# Microcontrolador.net
KiCad netlist of a schematic drawn in Altium Designer
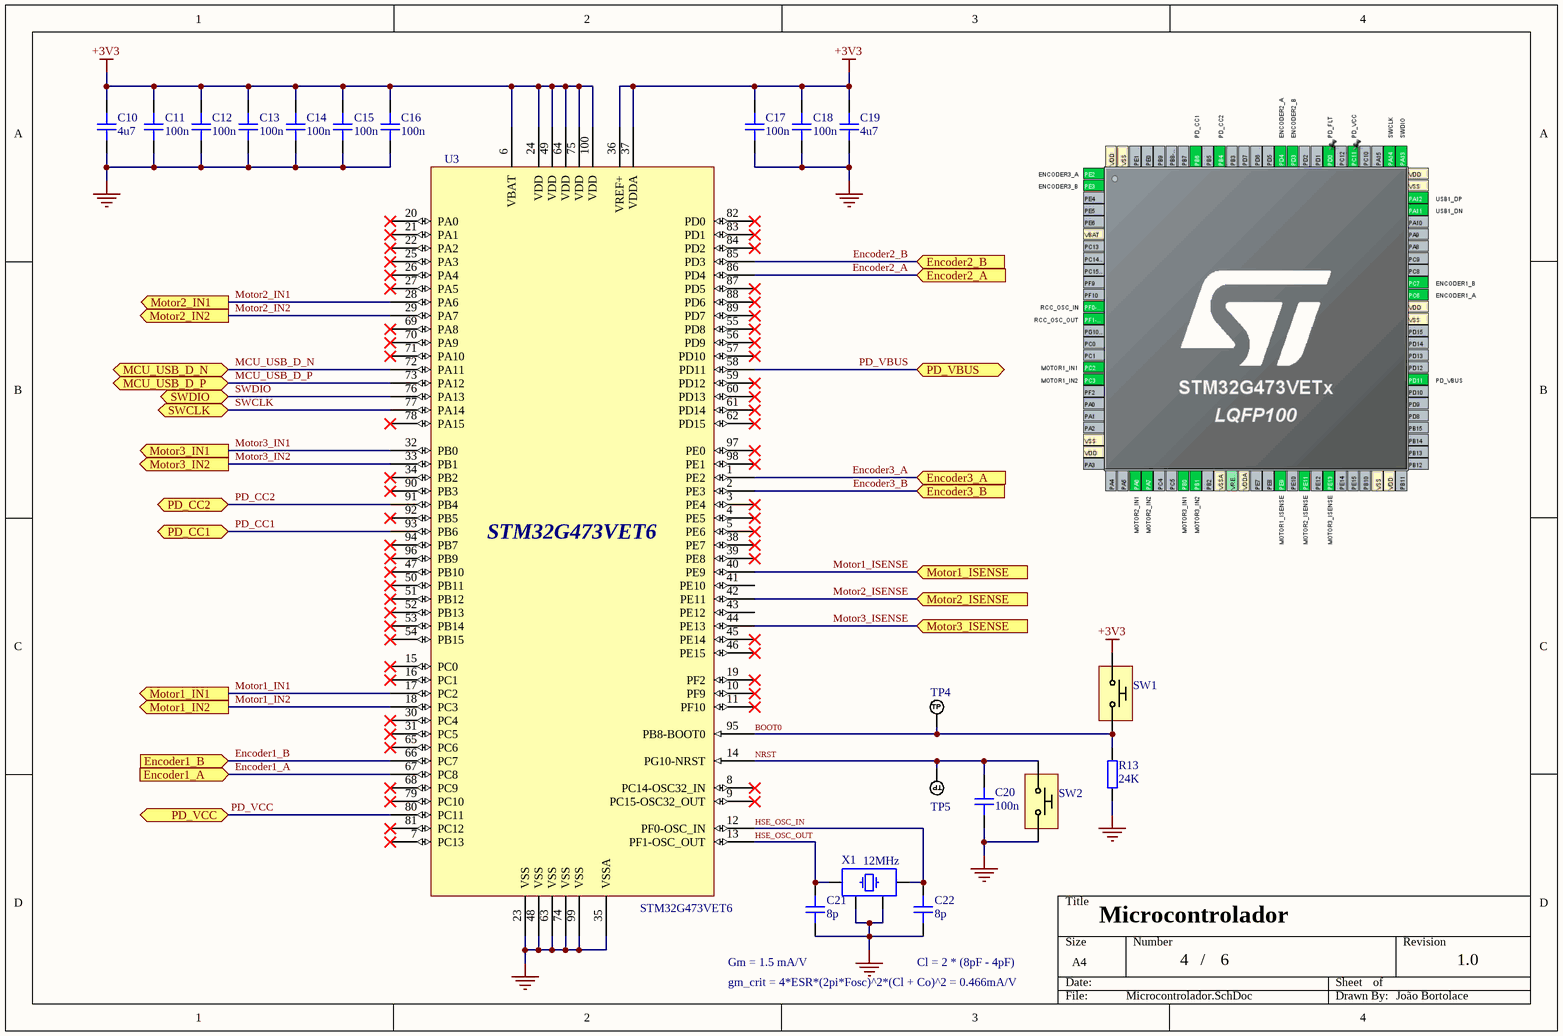
[diagram p0: Microcontrolador.SchDoc]

(export (version "E")
  (design (tool "Eeschema 10.0.6"))
  (components
    (comp (ref "C10")
      (value "4u7")
      (footprint "CAP_0805")
      (description "4.7uF ±10% 50V Ceramic Capacitor X5R 0805")
      (fields
        (field (name "MANUFACTURER") "Samsung Electro-Mechanics")
        (field (name "MANUFACTURER PART NUMBER") "CL21A475KBQNNNE")
      )
      (libsource (lib "Schematic-Lib-PhilsLab") (part "CAP_0805"))
    )
    (comp (ref "C11")
      (value "100n")
      (footprint "CAP_0402")
      (description "100nF ±10% 50V Ceramic Capacitor X7R 0402D 0402")
      (fields
        (field (name "MANUFACTURER") "muRata")
        (field (name "MANUFACTURER PART NUMBER") "GRM155R71H104KE14D")
      )
      (libsource (lib "Schematic-Lib-PhilsLab") (part "CAP_0402"))
    )
    (comp (ref "C12")
      (value "100n")
      (footprint "CAP_0402")
      (description "100nF ±10% 50V Ceramic Capacitor X7R 0402D 0402")
      (fields
        (field (name "MANUFACTURER") "muRata")
        (field (name "MANUFACTURER PART NUMBER") "GRM155R71H104KE14D")
      )
      (libsource (lib "Schematic-Lib-PhilsLab") (part "CAP_0402"))
    )
    (comp (ref "C13")
      (value "100n")
      (footprint "CAP_0402")
      (description "100nF ±10% 50V Ceramic Capacitor X7R 0402D 0402")
      (fields
        (field (name "MANUFACTURER") "muRata")
        (field (name "MANUFACTURER PART NUMBER") "GRM155R71H104KE14D")
      )
      (libsource (lib "Schematic-Lib-PhilsLab") (part "CAP_0402"))
    )
    (comp (ref "C14")
      (value "100n")
      (footprint "CAP_0402")
      (description "100nF ±10% 50V Ceramic Capacitor X7R 0402D 0402")
      (fields
        (field (name "MANUFACTURER") "muRata")
        (field (name "MANUFACTURER PART NUMBER") "GRM155R71H104KE14D")
      )
      (libsource (lib "Schematic-Lib-PhilsLab") (part "CAP_0402"))
    )
    (comp (ref "C15")
      (value "100n")
      (footprint "CAP_0402")
      (description "100nF ±10% 50V Ceramic Capacitor X7R 0402D 0402")
      (fields
        (field (name "MANUFACTURER") "muRata")
        (field (name "MANUFACTURER PART NUMBER") "GRM155R71H104KE14D")
      )
      (libsource (lib "Schematic-Lib-PhilsLab") (part "CAP_0402"))
    )
    (comp (ref "C16")
      (value "100n")
      (footprint "CAP_0402")
      (description "100nF ±10% 50V Ceramic Capacitor X7R 0402D 0402")
      (fields
        (field (name "MANUFACTURER") "muRata")
        (field (name "MANUFACTURER PART NUMBER") "GRM155R71H104KE14D")
      )
      (libsource (lib "Schematic-Lib-PhilsLab") (part "CAP_0402"))
    )
    (comp (ref "C17")
      (value "100n")
      (footprint "CAP_0402")
      (description "100nF ±10% 50V Ceramic Capacitor X7R 0402D 0402")
      (fields
        (field (name "MANUFACTURER") "muRata")
        (field (name "MANUFACTURER PART NUMBER") "GRM155R71H104KE14D")
      )
      (libsource (lib "Schematic-Lib-PhilsLab") (part "CAP_0402"))
    )
    (comp (ref "C18")
      (value "100n")
      (footprint "CAP_0402")
      (description "100nF ±10% 50V Ceramic Capacitor X7R 0402D 0402")
      (fields
        (field (name "MANUFACTURER") "muRata")
        (field (name "MANUFACTURER PART NUMBER") "GRM155R71H104KE14D")
      )
      (libsource (lib "Schematic-Lib-PhilsLab") (part "CAP_0402"))
    )
    (comp (ref "C19")
      (value "4u7")
      (footprint "CAP_0805")
      (description "4.7uF ±10% 50V Ceramic Capacitor X5R 0805")
      (fields
        (field (name "MANUFACTURER") "Samsung Electro-Mechanics")
        (field (name "MANUFACTURER PART NUMBER") "CL21A475KBQNNNE")
      )
      (libsource (lib "Schematic-Lib-PhilsLab") (part "CAP_0805"))
    )
    (comp (ref "C20")
      (value "100n")
      (footprint "CAP_0402")
      (description "100nF ±10% 50V Ceramic Capacitor X7R 0402D 0402")
      (fields
        (field (name "MANUFACTURER") "muRata")
        (field (name "MANUFACTURER PART NUMBER") "GRM155R71H104KE14D")
      )
      (libsource (lib "Schematic-Lib-PhilsLab") (part "CAP_0402"))
    )
    (comp (ref "C21")
      (value "8p")
      (footprint "CAP_0402")
      (description "8pF ±1% 50V Ceramic Capacitor C0G 0402")
      (fields
        (field (name "MANUFACTURER") "muRata")
        (field (name "MANUFACTURER PART NUMBER") "GCM1555C1H8R0FA16D")
      )
      (libsource (lib "Schematic-Lib-PhilsLab") (part "CAP_0402"))
    )
    (comp (ref "C22")
      (value "8p")
      (footprint "CAP_0402")
      (description "8pF ±1% 50V Ceramic Capacitor C0G 0402")
      (fields
        (field (name "MANUFACTURER") "muRata")
        (field (name "MANUFACTURER PART NUMBER") "GCM1555C1H8R0FA16D")
      )
      (libsource (lib "Schematic-Lib-PhilsLab") (part "CAP_0402"))
    )
    (comp (ref "R13")
      (value "24K")
      (footprint "RES_0402")
      (description "Resistor SMD 0402")
      (libsource (lib "Schematic-Lib-PhilsLab") (part "RES_0402"))
    )
    (comp (ref "SW1")
      (value "BOOT")
      (footprint "PTS815")
      (description "Tactile Switch SPST 400gf 2.5mm 4.2mm x 3.2mm Surface Mount")
      (fields
        (field (name "MANUFACTURER") "G-Switch")
        (field (name "MANUFACTURER PART NUMBER") "GT-TC048D-H025-L1")
      )
      (libsource (lib "Schematic-Lib-PhilsLab") (part "PTS815-SJM-250-SMTR-LFS"))
    )
    (comp (ref "SW2")
      (value "RST")
      (footprint "PTS815")
      (description "Tactile Switch SPST 400gf 2.5mm 4.2mm x 3.2mm Surface Mount")
      (fields
        (field (name "MANUFACTURER") "G-Switch")
        (field (name "MANUFACTURER PART NUMBER") "GT-TC048D-H025-L1")
      )
      (libsource (lib "Schematic-Lib-PhilsLab") (part "PTS815-SJM-250-SMTR-LFS"))
    )
    (comp (ref "TP4")
      (value "TP_NOBOM")
      (footprint "PAD_RND_1MM")
      (description "Test Point Round 1mm (NO BOM)")
      (libsource (lib "Schematic-Lib-PhilsLab") (part "TEST_POINT_RND_1MM"))
    )
    (comp (ref "TP5")
      (value "TP_NOBOM")
      (footprint "PAD_RND_1MM")
      (description "Test Point Round 1mm (NO BOM)")
      (libsource (lib "Schematic-Lib-PhilsLab") (part "TEST_POINT_RND_1MM"))
    )
    (comp (ref "U3")
      (value "STM32G473VET6")
      (footprint "LQFP100")
      (fields (field (name "MANUFACTURER") "STMicroelectronics"))
      (libsource (lib "Schematic-Lib-PhilsLab") (part "STM32G473VET6"))
    )
    (comp (ref "X1")
      (value "12MHz")
      (footprint "XTAL_3225")
      (description "Crystal 12MHz ±15ppm 8pF 120Ω SMD3225-4P")
      (fields (field (name "MANUFACTURER") "DIODES") (field (name "MANUFACTURER PART NUMBER") "FL1200138"))
      (libsource (lib "Schematic-Lib-PhilsLab") (part "TSX-3225_24.0000MF15X-AC"))
    )
  )
  (nets
    (net (code "1") (name "+3V3") (class "Default")
      (node (ref "C10") (pin "2") (pinfunction "2_2") (pintype "passive"))
      (node (ref "C11") (pin "2") (pinfunction "2_2") (pintype "passive"))
      (node (ref "C12") (pin "2") (pinfunction "2_2") (pintype "passive"))
      (node (ref "C13") (pin "2") (pinfunction "2_2") (pintype "passive"))
      (node (ref "C14") (pin "2") (pinfunction "2_2") (pintype "passive"))
      (node (ref "C15") (pin "2") (pinfunction "2_2") (pintype "passive"))
      (node (ref "C16") (pin "2") (pinfunction "2_2") (pintype "passive"))
      (node (ref "C17") (pin "2") (pinfunction "2_2") (pintype "passive"))
      (node (ref "C18") (pin "2") (pinfunction "2_2") (pintype "passive"))
      (node (ref "C19") (pin "2") (pinfunction "2_2") (pintype "passive"))
      (node (ref "SW1") (pin "1") (pinfunction "1_1") (pintype "passive"))
      (node (ref "U3") (pin "100") (pinfunction "VDD_100") (pintype "power_in"))
      (node (ref "U3") (pin "24") (pinfunction "VDD_24") (pintype "power_in"))
      (node (ref "U3") (pin "36") (pinfunction "VREF+_36") (pintype "power_in"))
      (node (ref "U3") (pin "37") (pinfunction "VDDA_37") (pintype "power_in"))
      (node (ref "U3") (pin "49") (pinfunction "VDD_49") (pintype "power_in"))
      (node (ref "U3") (pin "6") (pinfunction "VBAT_6") (pintype "power_in"))
      (node (ref "U3") (pin "64") (pinfunction "VDD_64") (pintype "power_in"))
      (node (ref "U3") (pin "75") (pinfunction "VDD_75") (pintype "power_in"))
    )
    (net (code "2") (name "/BOOT0") (class "Default")
      (node (ref "R13") (pin "2") (pinfunction "2_2") (pintype "passive"))
      (node (ref "SW1") (pin "2") (pinfunction "2_2") (pintype "passive"))
      (node (ref "TP4") (pin "1") (pinfunction "TP_1") (pintype "passive"))
      (node (ref "U3") (pin "95") (pinfunction "PB8-BOOT0_95") (pintype "input"))
    )
    (net (code "3") (name "/Encoder1_A") (class "Default")
      (node (ref "U3") (pin "67") (pinfunction "PC8_67") (pintype "bidirectional"))
    )
    (net (code "4") (name "/Encoder1_B") (class "Default")
      (node (ref "U3") (pin "66") (pinfunction "PC7_66") (pintype "bidirectional"))
    )
    (net (code "5") (name "/Encoder2_A") (class "Default")
      (node (ref "U3") (pin "86") (pinfunction "PD4_86") (pintype "bidirectional"))
    )
    (net (code "6") (name "/Encoder2_B") (class "Default")
      (node (ref "U3") (pin "85") (pinfunction "PD3_85") (pintype "bidirectional"))
    )
    (net (code "7") (name "/Encoder3_A") (class "Default")
      (node (ref "U3") (pin "1") (pinfunction "PE2_1") (pintype "bidirectional"))
    )
    (net (code "8") (name "/Encoder3_B") (class "Default")
      (node (ref "U3") (pin "2") (pinfunction "PE3_2") (pintype "bidirectional"))
    )
    (net (code "9") (name "/HSE_OSC_IN") (class "Default")
      (node (ref "C22") (pin "2") (pinfunction "2_2") (pintype "passive"))
      (node (ref "U3") (pin "12") (pinfunction "PF0-OSC_IN_12") (pintype "bidirectional"))
      (node (ref "X1") (pin "3") (pinfunction "3_3") (pintype "passive"))
    )
    (net (code "10") (name "/HSE_OSC_OUT") (class "Default")
      (node (ref "C21") (pin "2") (pinfunction "2_2") (pintype "passive"))
      (node (ref "U3") (pin "13") (pinfunction "PF1-OSC_OUT_13") (pintype "bidirectional"))
      (node (ref "X1") (pin "1") (pinfunction "1_1") (pintype "passive"))
    )
    (net (code "11") (name "/MCU_USB_D_N") (class "Default")
      (node (ref "U3") (pin "72") (pinfunction "PA11_72") (pintype "bidirectional"))
    )
    (net (code "12") (name "/MCU_USB_D_P") (class "Default")
      (node (ref "U3") (pin "73") (pinfunction "PA12_73") (pintype "bidirectional"))
    )
    (net (code "13") (name "/Motor1_IN1") (class "Default")
      (node (ref "U3") (pin "17") (pinfunction "PC2_17") (pintype "bidirectional"))
    )
    (net (code "14") (name "/Motor1_IN2") (class "Default")
      (node (ref "U3") (pin "18") (pinfunction "PC3_18") (pintype "bidirectional"))
    )
    (net (code "15") (name "/Motor1_ISENSE") (class "Default")
      (node (ref "U3") (pin "40") (pinfunction "PE9_40") (pintype "bidirectional"))
    )
    (net (code "16") (name "/Motor2_IN1") (class "Default")
      (node (ref "U3") (pin "28") (pinfunction "PA6_28") (pintype "bidirectional"))
    )
    (net (code "17") (name "/Motor2_IN2") (class "Default")
      (node (ref "U3") (pin "29") (pinfunction "PA7_29") (pintype "bidirectional"))
    )
    (net (code "18") (name "/Motor2_ISENSE") (class "Default")
      (node (ref "U3") (pin "42") (pinfunction "PE11_42") (pintype "bidirectional"))
    )
    (net (code "19") (name "/Motor3_IN1") (class "Default")
      (node (ref "U3") (pin "32") (pinfunction "PB0_32") (pintype "bidirectional"))
    )
    (net (code "20") (name "/Motor3_IN2") (class "Default")
      (node (ref "U3") (pin "33") (pinfunction "PB1_33") (pintype "bidirectional"))
    )
    (net (code "21") (name "/Motor3_ISENSE") (class "Default")
      (node (ref "U3") (pin "44") (pinfunction "PE13_44") (pintype "bidirectional"))
    )
    (net (code "22") (name "/NRST") (class "Default")
      (node (ref "C20") (pin "2") (pinfunction "2_2") (pintype "passive"))
      (node (ref "SW2") (pin "1") (pinfunction "1_1") (pintype "passive"))
      (node (ref "TP5") (pin "1") (pinfunction "TP_1") (pintype "passive"))
      (node (ref "U3") (pin "14") (pinfunction "PG10-NRST_14") (pintype "input"))
    )
    (net (code "23") (name "/PD_CC1") (class "Default")
      (node (ref "U3") (pin "93") (pinfunction "PB6_93") (pintype "bidirectional"))
    )
    (net (code "24") (name "/PD_CC2") (class "Default")
      (node (ref "U3") (pin "91") (pinfunction "PB4_91") (pintype "bidirectional"))
    )
    (net (code "25") (name "/PD_VBUS") (class "Default")
      (node (ref "U3") (pin "58") (pinfunction "PD11_58") (pintype "bidirectional"))
    )
    (net (code "26") (name "/PD_VCC") (class "Default")
      (node (ref "U3") (pin "80") (pinfunction "PC11_80") (pintype "bidirectional"))
    )
    (net (code "27") (name "/SWCLK") (class "Default")
      (node (ref "U3") (pin "77") (pinfunction "PA14_77") (pintype "bidirectional"))
    )
    (net (code "28") (name "/SWDIO") (class "Default")
      (node (ref "U3") (pin "76") (pinfunction "PA13_76") (pintype "bidirectional"))
    )
    (net (code "29") (name "GND") (class "Default")
      (node (ref "C10") (pin "1") (pinfunction "1_1") (pintype "passive"))
      (node (ref "C11") (pin "1") (pinfunction "1_1") (pintype "passive"))
      (node (ref "C12") (pin "1") (pinfunction "1_1") (pintype "passive"))
      (node (ref "C13") (pin "1") (pinfunction "1_1") (pintype "passive"))
      (node (ref "C14") (pin "1") (pinfunction "1_1") (pintype "passive"))
      (node (ref "C15") (pin "1") (pinfunction "1_1") (pintype "passive"))
      (node (ref "C16") (pin "1") (pinfunction "1_1") (pintype "passive"))
      (node (ref "C17") (pin "1") (pinfunction "1_1") (pintype "passive"))
      (node (ref "C18") (pin "1") (pinfunction "1_1") (pintype "passive"))
      (node (ref "C19") (pin "1") (pinfunction "1_1") (pintype "passive"))
      (node (ref "C20") (pin "1") (pinfunction "1_1") (pintype "passive"))
      (node (ref "C21") (pin "1") (pinfunction "1_1") (pintype "passive"))
      (node (ref "C22") (pin "1") (pinfunction "1_1") (pintype "passive"))
      (node (ref "R13") (pin "1") (pinfunction "1_1") (pintype "passive"))
      (node (ref "SW2") (pin "2") (pinfunction "2_2") (pintype "passive"))
      (node (ref "U3") (pin "23") (pinfunction "VSS_23") (pintype "power_in"))
      (node (ref "U3") (pin "35") (pinfunction "VSSA_35") (pintype "power_in"))
      (node (ref "U3") (pin "48") (pinfunction "VSS_48") (pintype "power_in"))
      (node (ref "U3") (pin "63") (pinfunction "VSS_63") (pintype "power_in"))
      (node (ref "U3") (pin "74") (pinfunction "VSS_74") (pintype "power_in"))
      (node (ref "U3") (pin "99") (pinfunction "VSS_99") (pintype "power_in"))
      (node (ref "X1") (pin "2") (pinfunction "2_2") (pintype "passive"))
      (node (ref "X1") (pin "4") (pinfunction "4_4") (pintype "passive"))
    )
    (net (code "30") (name "unconnected-(U3-PA0-Pad20)") (class "Default")
      (node (ref "U3") (pin "20") (pinfunction "PA0_20") (pintype "bidirectional+no_connect"))
    )
    (net (code "31") (name "unconnected-(U3-PA1-Pad21)") (class "Default")
      (node (ref "U3") (pin "21") (pinfunction "PA1_21") (pintype "bidirectional+no_connect"))
    )
    (net (code "32") (name "unconnected-(U3-PA2-Pad22)") (class "Default")
      (node (ref "U3") (pin "22") (pinfunction "PA2_22") (pintype "bidirectional+no_connect"))
    )
    (net (code "33") (name "unconnected-(U3-PA3-Pad25)") (class "Default")
      (node (ref "U3") (pin "25") (pinfunction "PA3_25") (pintype "bidirectional+no_connect"))
    )
    (net (code "34") (name "unconnected-(U3-PA4-Pad26)") (class "Default")
      (node (ref "U3") (pin "26") (pinfunction "PA4_26") (pintype "bidirectional+no_connect"))
    )
    (net (code "35") (name "unconnected-(U3-PA5-Pad27)") (class "Default")
      (node (ref "U3") (pin "27") (pinfunction "PA5_27") (pintype "bidirectional+no_connect"))
    )
    (net (code "36") (name "unconnected-(U3-PA8-Pad69)") (class "Default")
      (node (ref "U3") (pin "69") (pinfunction "PA8_69") (pintype "bidirectional+no_connect"))
    )
    (net (code "37") (name "unconnected-(U3-PA9-Pad70)") (class "Default")
      (node (ref "U3") (pin "70") (pinfunction "PA9_70") (pintype "bidirectional+no_connect"))
    )
    (net (code "38") (name "unconnected-(U3-PA10-Pad71)") (class "Default")
      (node (ref "U3") (pin "71") (pinfunction "PA10_71") (pintype "bidirectional+no_connect"))
    )
    (net (code "39") (name "unconnected-(U3-PA15-Pad78)") (class "Default")
      (node (ref "U3") (pin "78") (pinfunction "PA15_78") (pintype "bidirectional+no_connect"))
    )
    (net (code "40") (name "unconnected-(U3-PB2-Pad34)") (class "Default")
      (node (ref "U3") (pin "34") (pinfunction "PB2_34") (pintype "bidirectional+no_connect"))
    )
    (net (code "41") (name "unconnected-(U3-PB3-Pad90)") (class "Default")
      (node (ref "U3") (pin "90") (pinfunction "PB3_90") (pintype "bidirectional+no_connect"))
    )
    (net (code "42") (name "unconnected-(U3-PB5-Pad92)") (class "Default")
      (node (ref "U3") (pin "92") (pinfunction "PB5_92") (pintype "bidirectional+no_connect"))
    )
    (net (code "43") (name "unconnected-(U3-PB7-Pad94)") (class "Default")
      (node (ref "U3") (pin "94") (pinfunction "PB7_94") (pintype "bidirectional+no_connect"))
    )
    (net (code "44") (name "unconnected-(U3-PB9-Pad96)") (class "Default")
      (node (ref "U3") (pin "96") (pinfunction "PB9_96") (pintype "bidirectional+no_connect"))
    )
    (net (code "45") (name "unconnected-(U3-PB10-Pad47)") (class "Default")
      (node (ref "U3") (pin "47") (pinfunction "PB10_47") (pintype "bidirectional+no_connect"))
    )
    (net (code "46") (name "unconnected-(U3-PB11-Pad50)") (class "Default")
      (node (ref "U3") (pin "50") (pinfunction "PB11_50") (pintype "bidirectional+no_connect"))
    )
    (net (code "47") (name "unconnected-(U3-PB12-Pad51)") (class "Default")
      (node (ref "U3") (pin "51") (pinfunction "PB12_51") (pintype "bidirectional+no_connect"))
    )
    (net (code "48") (name "unconnected-(U3-PB13-Pad52)") (class "Default")
      (node (ref "U3") (pin "52") (pinfunction "PB13_52") (pintype "bidirectional+no_connect"))
    )
    (net (code "49") (name "unconnected-(U3-PB14-Pad53)") (class "Default")
      (node (ref "U3") (pin "53") (pinfunction "PB14_53") (pintype "bidirectional+no_connect"))
    )
    (net (code "50") (name "unconnected-(U3-PB15-Pad54)") (class "Default")
      (node (ref "U3") (pin "54") (pinfunction "PB15_54") (pintype "bidirectional+no_connect"))
    )
    (net (code "51") (name "unconnected-(U3-PC0-Pad15)") (class "Default")
      (node (ref "U3") (pin "15") (pinfunction "PC0_15") (pintype "bidirectional+no_connect"))
    )
    (net (code "52") (name "unconnected-(U3-PC1-Pad16)") (class "Default")
      (node (ref "U3") (pin "16") (pinfunction "PC1_16") (pintype "bidirectional+no_connect"))
    )
    (net (code "53") (name "unconnected-(U3-PC4-Pad30)") (class "Default")
      (node (ref "U3") (pin "30") (pinfunction "PC4_30") (pintype "bidirectional+no_connect"))
    )
    (net (code "54") (name "unconnected-(U3-PC5-Pad31)") (class "Default")
      (node (ref "U3") (pin "31") (pinfunction "PC5_31") (pintype "bidirectional+no_connect"))
    )
    (net (code "55") (name "unconnected-(U3-PC6-Pad65)") (class "Default")
      (node (ref "U3") (pin "65") (pinfunction "PC6_65") (pintype "bidirectional+no_connect"))
    )
    (net (code "56") (name "unconnected-(U3-PC9-Pad68)") (class "Default")
      (node (ref "U3") (pin "68") (pinfunction "PC9_68") (pintype "bidirectional+no_connect"))
    )
    (net (code "57") (name "unconnected-(U3-PC10-Pad79)") (class "Default")
      (node (ref "U3") (pin "79") (pinfunction "PC10_79") (pintype "bidirectional+no_connect"))
    )
    (net (code "58") (name "unconnected-(U3-PC12-Pad81)") (class "Default")
      (node (ref "U3") (pin "81") (pinfunction "PC12_81") (pintype "bidirectional+no_connect"))
    )
    (net (code "59") (name "unconnected-(U3-PC13-Pad7)") (class "Default")
      (node (ref "U3") (pin "7") (pinfunction "PC13_7") (pintype "bidirectional+no_connect"))
    )
    (net (code "60") (name "unconnected-(U3-PC14-OSC32_IN-Pad8)") (class "Default")
      (node (ref "U3") (pin "8") (pinfunction "PC14-OSC32_IN_8") (pintype "bidirectional+no_connect"))
    )
    (net (code "61") (name "unconnected-(U3-PC15-OSC32_OUT-Pad9)") (class "Default")
      (node (ref "U3") (pin "9") (pinfunction "PC15-OSC32_OUT_9") (pintype "bidirectional+no_connect"))
    )
    (net (code "62") (name "unconnected-(U3-PD0-Pad82)") (class "Default")
      (node (ref "U3") (pin "82") (pinfunction "PD0_82") (pintype "bidirectional+no_connect"))
    )
    (net (code "63") (name "unconnected-(U3-PD1-Pad83)") (class "Default")
      (node (ref "U3") (pin "83") (pinfunction "PD1_83") (pintype "bidirectional+no_connect"))
    )
    (net (code "64") (name "unconnected-(U3-PD2-Pad84)") (class "Default")
      (node (ref "U3") (pin "84") (pinfunction "PD2_84") (pintype "bidirectional+no_connect"))
    )
    (net (code "65") (name "unconnected-(U3-PD5-Pad87)") (class "Default")
      (node (ref "U3") (pin "87") (pinfunction "PD5_87") (pintype "bidirectional+no_connect"))
    )
    (net (code "66") (name "unconnected-(U3-PD6-Pad88)") (class "Default")
      (node (ref "U3") (pin "88") (pinfunction "PD6_88") (pintype "bidirectional+no_connect"))
    )
    (net (code "67") (name "unconnected-(U3-PD7-Pad89)") (class "Default")
      (node (ref "U3") (pin "89") (pinfunction "PD7_89") (pintype "bidirectional+no_connect"))
    )
    (net (code "68") (name "unconnected-(U3-PD8-Pad55)") (class "Default")
      (node (ref "U3") (pin "55") (pinfunction "PD8_55") (pintype "bidirectional+no_connect"))
    )
    (net (code "69") (name "unconnected-(U3-PD9-Pad56)") (class "Default")
      (node (ref "U3") (pin "56") (pinfunction "PD9_56") (pintype "bidirectional+no_connect"))
    )
    (net (code "70") (name "unconnected-(U3-PD10-Pad57)") (class "Default")
      (node (ref "U3") (pin "57") (pinfunction "PD10_57") (pintype "bidirectional+no_connect"))
    )
    (net (code "71") (name "unconnected-(U3-PD12-Pad59)") (class "Default")
      (node (ref "U3") (pin "59") (pinfunction "PD12_59") (pintype "bidirectional+no_connect"))
    )
    (net (code "72") (name "unconnected-(U3-PD13-Pad60)") (class "Default")
      (node (ref "U3") (pin "60") (pinfunction "PD13_60") (pintype "bidirectional+no_connect"))
    )
    (net (code "73") (name "unconnected-(U3-PD14-Pad61)") (class "Default")
      (node (ref "U3") (pin "61") (pinfunction "PD14_61") (pintype "bidirectional+no_connect"))
    )
    (net (code "74") (name "unconnected-(U3-PD15-Pad62)") (class "Default")
      (node (ref "U3") (pin "62") (pinfunction "PD15_62") (pintype "bidirectional+no_connect"))
    )
    (net (code "75") (name "unconnected-(U3-PE0-Pad97)") (class "Default")
      (node (ref "U3") (pin "97") (pinfunction "PE0_97") (pintype "bidirectional+no_connect"))
    )
    (net (code "76") (name "unconnected-(U3-PE1-Pad98)") (class "Default")
      (node (ref "U3") (pin "98") (pinfunction "PE1_98") (pintype "bidirectional+no_connect"))
    )
    (net (code "77") (name "unconnected-(U3-PE4-Pad3)") (class "Default")
      (node (ref "U3") (pin "3") (pinfunction "PE4_3") (pintype "bidirectional+no_connect"))
    )
    (net (code "78") (name "unconnected-(U3-PE5-Pad4)") (class "Default")
      (node (ref "U3") (pin "4") (pinfunction "PE5_4") (pintype "bidirectional+no_connect"))
    )
    (net (code "79") (name "unconnected-(U3-PE6-Pad5)") (class "Default")
      (node (ref "U3") (pin "5") (pinfunction "PE6_5") (pintype "bidirectional+no_connect"))
    )
    (net (code "80") (name "unconnected-(U3-PE7-Pad38)") (class "Default")
      (node (ref "U3") (pin "38") (pinfunction "PE7_38") (pintype "bidirectional+no_connect"))
    )
    (net (code "81") (name "unconnected-(U3-PE8-Pad39)") (class "Default")
      (node (ref "U3") (pin "39") (pinfunction "PE8_39") (pintype "bidirectional+no_connect"))
    )
    (net (code "82") (name "unconnected-(U3-PE10-Pad41)") (class "Default")
      (node (ref "U3") (pin "41") (pinfunction "PE10_41") (pintype "bidirectional"))
    )
    (net (code "83") (name "unconnected-(U3-PE12-Pad43)") (class "Default")
      (node (ref "U3") (pin "43") (pinfunction "PE12_43") (pintype "bidirectional"))
    )
    (net (code "84") (name "unconnected-(U3-PE14-Pad45)") (class "Default")
      (node (ref "U3") (pin "45") (pinfunction "PE14_45") (pintype "bidirectional+no_connect"))
    )
    (net (code "85") (name "unconnected-(U3-PE15-Pad46)") (class "Default")
      (node (ref "U3") (pin "46") (pinfunction "PE15_46") (pintype "bidirectional+no_connect"))
    )
    (net (code "86") (name "unconnected-(U3-PF2-Pad19)") (class "Default")
      (node (ref "U3") (pin "19") (pinfunction "PF2_19") (pintype "bidirectional+no_connect"))
    )
    (net (code "87") (name "unconnected-(U3-PF9-Pad10)") (class "Default")
      (node (ref "U3") (pin "10") (pinfunction "PF9_10") (pintype "bidirectional+no_connect"))
    )
    (net (code "88") (name "unconnected-(U3-PF10-Pad11)") (class "Default")
      (node (ref "U3") (pin "11") (pinfunction "PF10_11") (pintype "bidirectional+no_connect"))
    )
  )
)
